# Nixie_Embedded_Controller.net
KiCad netlist of a schematic drawn in Altium Designer
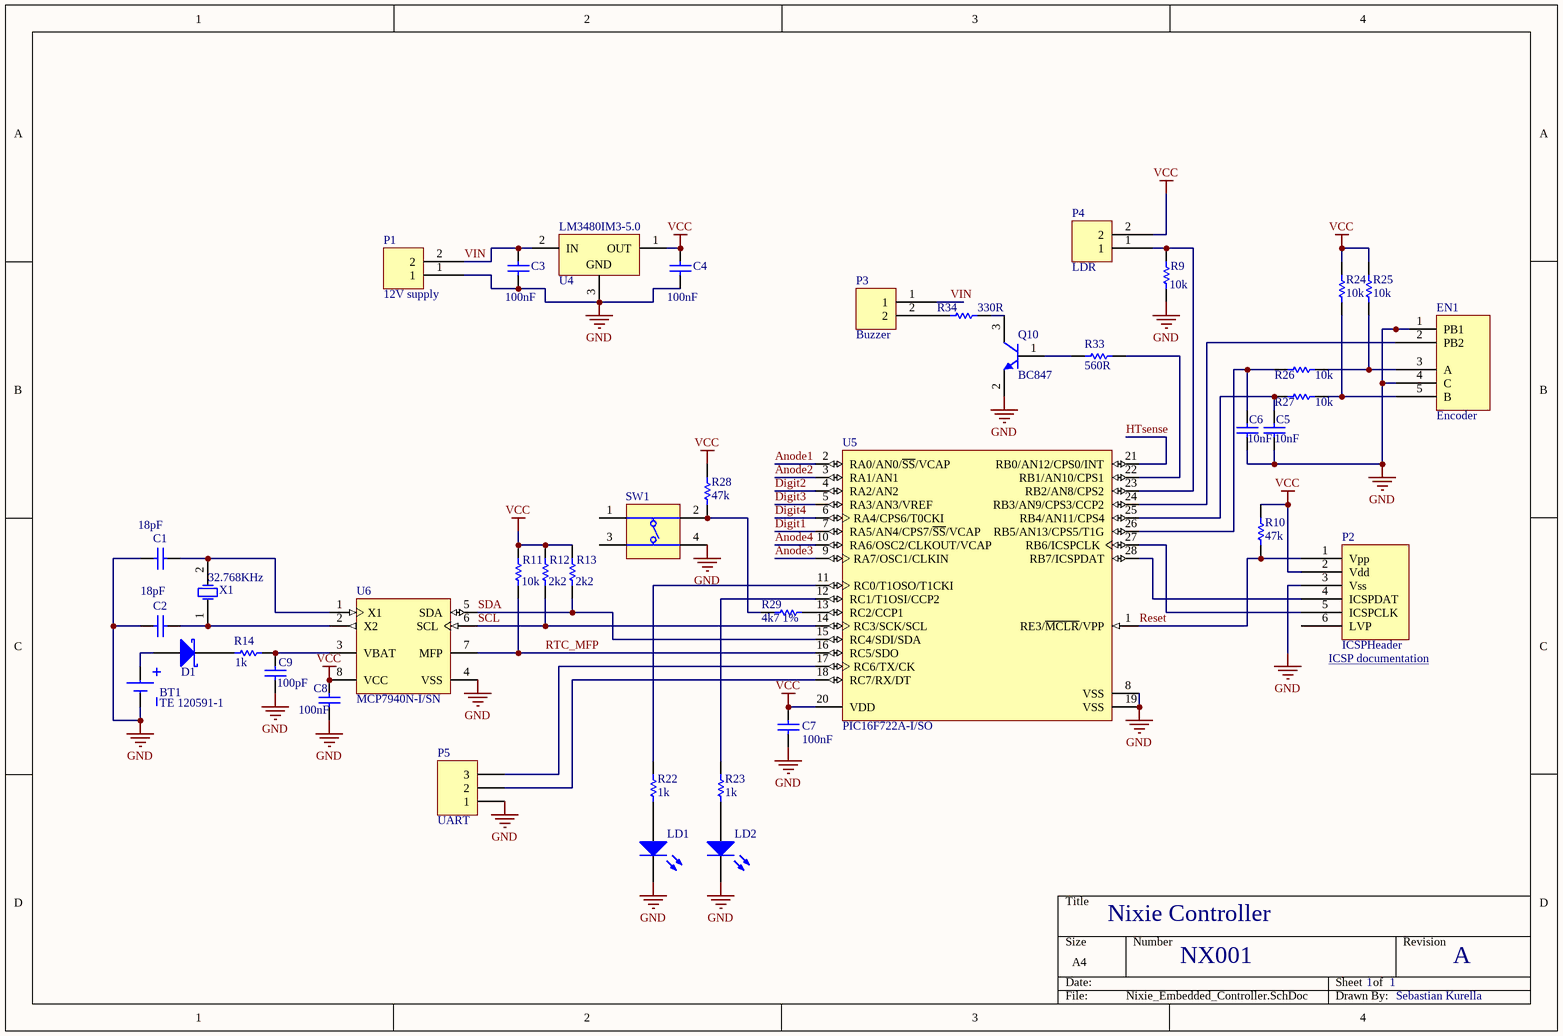
[diagram p0: Nixie_Embedded_Controller.SchDoc]

(export (version "E")
  (design (tool "Eeschema 10.0.6"))
  (components
    (comp (ref "BT1")
      (value "TE 120591-1")
      (footprint "TE-120591-1")
      (libsource (lib "Nixie_Controller") (part "TECO-120591-1-2"))
    )
    (comp (ref "C1")
      (value "18pF")
      (footprint "CAPC0805(2012)100_M")
      (description "CAP 18pF 16V ±5% 0805 (2012 Metric) Thickness 1mm SMD")
      (fields (field (name "TOLERANCE") "±5%") (field (name "Comment") "CAP 18pF 16V 0805(2012)"))
      (libsource (lib "Altium Content Vault") (part "CMP-1036-01121-1"))
    )
    (comp (ref "C2")
      (value "18pF")
      (footprint "CAPC0805(2012)100_M")
      (description "CAP 18pF 16V ±5% 0805 (2012 Metric) Thickness 1mm SMD")
      (fields (field (name "TOLERANCE") "±5%") (field (name "Comment") "CAP 18pF 16V 0805(2012)"))
      (libsource (lib "Altium Content Vault") (part "CMP-1036-01121-1"))
    )
    (comp (ref "C3")
      (value "100nF")
      (footprint "CAPC0805(2012)100_M")
      (description "CAP 100nF 16V ±20% 0805 (2012 Metric) Thickness 1mm SMD")
      (fields (field (name "TOLERANCE") "±20%") (field (name "Comment") "CAP 100nF 16V 0805(2012)"))
      (libsource (lib "Altium Content Vault") (part "CMP-1036-04405-1"))
    )
    (comp (ref "C4")
      (value "100nF")
      (footprint "CAPC0805(2012)100_M")
      (description "CAP 100nF 16V ±20% 0805 (2012 Metric) Thickness 1mm SMD")
      (fields (field (name "TOLERANCE") "±20%") (field (name "Comment") "CAP 100nF 16V 0805(2012)"))
      (libsource (lib "Altium Content Vault") (part "CMP-1036-04405-1"))
    )
    (comp (ref "C5")
      (value "10nF")
      (footprint "CAPC0805(2012)100_M")
      (description "CAP 10nF 16V ±10% 0805 (2012 Metric) Thickness 1mm SMD")
      (fields (field (name "TOLERANCE") "±10%"))
      (libsource (lib "Altium Content Vault") (part "CMP-1036-03820-1"))
    )
    (comp (ref "C6")
      (value "10nF")
      (footprint "CAPC0805(2012)100_M")
      (description "CAP 10nF 16V ±10% 0805 (2012 Metric) Thickness 1mm SMD")
      (fields (field (name "TOLERANCE") "±10%"))
      (libsource (lib "Altium Content Vault") (part "CMP-1036-03820-1"))
    )
    (comp (ref "C7")
      (value "100nF")
      (footprint "CAPC0805(2012)100_M")
      (description "CAP 100nF 10V ±5% 0805 (2012 Metric) Thickness 1mm SMD")
      (fields (field (name "TOLERANCE") "±5%") (field (name "Comment") "CAP 100nF 10V 0805(2012)"))
      (libsource (lib "Altium Content Vault") (part "CAP"))
    )
    (comp (ref "C8")
      (value "100nF")
      (footprint "CAPC0805(2012)100_M")
      (description "CAP 100nF 10V ±5% 0805 (2012 Metric) Thickness 1mm SMD")
      (fields (field (name "TOLERANCE") "±5%") (field (name "Comment") "CAP 100nF 10V 0805(2012)"))
      (libsource (lib "Altium Content Vault") (part "CMP-1036-04393-1"))
    )
    (comp (ref "C9")
      (value "100pF")
      (footprint "CAPC0805(2012)100_M")
      (description "CAP 100pF 10V ±2% 0805 (2012 Metric) Thickness 1mm SMD")
      (fields (field (name "TOLERANCE") "±2%") (field (name "Comment") "CAP 100pF 10V 0805(2012)"))
      (libsource (lib "Altium Content Vault") (part "CMP-1036-01930-1"))
    )
    (comp (ref "D1")
      (value "Schottky")
      (footprint "SOD-123")
      (libsource (lib "Nixie_Controller") (part "Schottky"))
    )
    (comp (ref "EN1")
      (value "Encoder")
      (footprint "BOURNS_PEC12R_ENCODER")
      (libsource (lib "Nixie_Controller") (part "Encoder"))
    )
    (comp (ref "LD1")
      (value "150080GS75000")
      (footprint "0805_A")
      (description "SMD mono-color Chip LED, WL-SMCW, Green")
      (fields (field (name "MANUFACTURER") "Wuerth Elektronik"))
      (libsource (lib "Altium Content Vault") (part "CMP-1426-00007-1"))
    )
    (comp (ref "LD2")
      (value "150080RS75000")
      (footprint "0805_A")
      (description "SMD mono-color Chip LED, WL-SMCW, Red")
      (fields (field (name "MANUFACTURER") "Wuerth Elektronik"))
      (libsource (lib "Altium Content Vault") (part "CMP-1426-00011-1"))
    )
    (comp (ref "P1")
      (value "12V supply")
      (footprint "2pos terminal block 3.5mm")
      (description "TE 1776275-2")
      (libsource (lib "") (part "2pos terminal block 3.5mm_1"))
    )
    (comp (ref "P2")
      (value "ICSPHeader")
      (footprint "ICSPHDR")
      (libsource (lib "Nixie_Controller") (part "ICSPHeader"))
    )
    (comp (ref "P3")
      (value "Buzzer")
      (footprint "2pos terminal block 3.5mm")
      (description "TE 1776275-2")
      (libsource (lib "Nixie_Controller") (part "2pos terminal block 3.5mm"))
    )
    (comp (ref "P4")
      (value "LDR")
      (footprint "Header 1x2")
      (description "TE 640456-2")
      (libsource (lib "Nixie_Controller") (part "Header 1x2"))
    )
    (comp (ref "P5")
      (value "UART")
      (footprint "HDR1X3")
      (description "Header, 3-Pin")
      (fields (field (name "PUBLISHER") "Altium Limited"))
      (libsource (lib "Miscellaneous Connectors") (part "Header 3"))
    )
    (comp (ref "Q10")
      (value "BC847")
      (footprint "ONSC-SOT-23-3-318-08_V")
      (description "General Purpose Transistor, NPN Silicon, 3-Pin SOT-23, Tape and Reel")
      (fields (field (name "MANUFACTURER") "On Semiconductor") (field (name "PARTNUMBER") "BC847ALT1"))
      (libsource (lib "Altium Content Vault") (part "ONSC-NPN-B1E2C3-3"))
    )
    (comp (ref "R9")
      (value "10k")
      (footprint "RESC0805(2012)_M")
      (description "10K 0.125W 5% 0805 (2012 Metric)  SMD")
      (fields (field (name "POWER") "0.125 W") (field (name "TOLERANCE") "5 %"))
      (libsource (lib "Altium Content Vault") (part "CMP-1013-00098-1"))
    )
    (comp (ref "R10")
      (value "47k")
      (footprint "RESC0805(2012)_M")
      (description "47K 0.125W 5% 0805 (2012 Metric)  SMD")
      (fields (field (name "TOLERANCE") "5 %") (field (name "POWER") "0.125 W"))
      (libsource (lib "Altium Content Vault") (part "CMP-1013-00114-1"))
    )
    (comp (ref "R11")
      (value "10k")
      (footprint "RESC0805(2012)_M")
      (description "10K 0.125W 5% 0805 (2012 Metric)  SMD")
      (fields (field (name "POWER") "0.125 W") (field (name "TOLERANCE") "5 %"))
      (libsource (lib "Altium Content Vault") (part "CMP-1013-00098-1"))
    )
    (comp (ref "R12")
      (value "2k2")
      (footprint "RESC0805(2012)_M")
      (description "2K2 0.125W 5% 0805 (2012 Metric)  SMD")
      (fields (field (name "POWER") "0.125 W") (field (name "TOLERANCE") "5 %"))
      (libsource (lib "Altium Content Vault") (part "CMP-1013-00082-1"))
    )
    (comp (ref "R13")
      (value "2k2")
      (footprint "RESC0805(2012)_M")
      (description "2K2 0.125W 5% 0805 (2012 Metric)  SMD")
      (fields (field (name "POWER") "0.125 W") (field (name "TOLERANCE") "5 %"))
      (libsource (lib "Altium Content Vault") (part "CMP-1013-00082-1"))
    )
    (comp (ref "R14")
      (value "1k")
      (footprint "RESC0805(2012)_M")
      (description "1K 0.125W 5% 0805 (2012 Metric)  SMD")
      (fields (field (name "POWER") "0.125 W") (field (name "TOLERANCE") "5 %"))
      (libsource (lib "Altium Content Vault") (part "CMP-1013-00074-1"))
    )
    (comp (ref "R22")
      (value "1k")
      (footprint "RESC0805(2012)_M")
      (description "1K 0.125W 5% 0805 (2012 Metric)  SMD")
      (fields (field (name "POWER") "0.125 W") (field (name "TOLERANCE") "5 %"))
      (libsource (lib "Altium Content Vault") (part "CMP-1013-00074-1"))
    )
    (comp (ref "R23")
      (value "1k")
      (footprint "RESC0805(2012)_M")
      (description "1K 0.125W 5% 0805 (2012 Metric)  SMD")
      (fields (field (name "POWER") "0.125 W") (field (name "TOLERANCE") "5 %"))
      (libsource (lib "Altium Content Vault") (part "CMP-1013-00074-1"))
    )
    (comp (ref "R24")
      (value "10k")
      (footprint "RESC0805(2012)_M")
      (description "10K 0.125W 5% 0805 (2012 Metric)  SMD")
      (fields (field (name "POWER") "0.125 W") (field (name "TOLERANCE") "5 %"))
      (libsource (lib "Altium Content Vault") (part "CMP-1013-00098-1"))
    )
    (comp (ref "R25")
      (value "10k")
      (footprint "RESC0805(2012)_M")
      (description "10K 0.125W 5% 0805 (2012 Metric)  SMD")
      (fields (field (name "POWER") "0.125 W") (field (name "TOLERANCE") "5 %"))
      (libsource (lib "Altium Content Vault") (part "CMP-1013-00098-1"))
    )
    (comp (ref "R26")
      (value "10k")
      (footprint "RESC0805(2012)_M")
      (description "10K 0.125W 5% 0805 (2012 Metric)  SMD")
      (fields (field (name "POWER") "0.125 W") (field (name "TOLERANCE") "5 %"))
      (libsource (lib "Altium Content Vault") (part "CMP-1013-00098-1"))
    )
    (comp (ref "R27")
      (value "10k")
      (footprint "RESC0805(2012)_M")
      (description "10K 0.125W 5% 0805 (2012 Metric)  SMD")
      (fields (field (name "POWER") "0.125 W") (field (name "TOLERANCE") "5 %"))
      (libsource (lib "Altium Content Vault") (part "CMP-1013-00098-1"))
    )
    (comp (ref "R28")
      (value "47k")
      (footprint "RESC0805(2012)_L")
      (description "47K 0.125W 5% 0805 (2012 Metric)  SMD")
      (fields (field (name "TOLERANCE") "5 %") (field (name "POWER") "0.125 W"))
      (libsource (lib "Altium Content Vault") (part "RES"))
    )
    (comp (ref "R29")
      (value "4k7 1%")
      (footprint "RESC0805(2012)_M")
      (description "4K7 0.125W 1% 0805 (2012 Metric)  SMD")
      (fields (field (name "POWER") "0.125 W") (field (name "TOLERANCE") "1 %"))
      (libsource (lib "Altium Content Vault") (part "CMP-1013-00586-1"))
    )
    (comp (ref "R33")
      (value "560R")
      (footprint "RESC0805(2012)_M")
      (description "560R 0.125W 5% 0805 (2012 Metric)  SMD")
      (fields (field (name "POWER") "0.125 W") (field (name "TOLERANCE") "5 %"))
      (libsource (lib "Altium Content Vault") (part "CMP-1013-00068-1"))
    )
    (comp (ref "R34")
      (value "330R")
      (footprint "RESC0805(2012)_M")
      (description "330R 0.125W 5% 0805 (2012 Metric)  SMD")
      (fields (field (name "TOLERANCE") "5 %") (field (name "POWER") "0.125 W"))
      (libsource (lib "Altium Content Vault") (part "CMP-1013-00062-1"))
    )
    (comp (ref "SW1")
      (value "DTSM-61NT/R")
      (footprint "DIPT-DTSM-6_V")
      (description "Switch, SPNO Push Button SMD")
      (fields (field (name "MANUFACTURER") "Diptronics"))
      (libsource (lib "Altium Content Vault") (part "CMP-0306-00001-1"))
    )
    (comp (ref "U4")
      (value "LM3480IM3-5.0")
      (footprint "MF03A_N")
      (description "100 mA, Quasi Low-Dropout Linear Voltage Regulator, 3-pin SOT-23, Pb-Free")
      (fields (field (name "MANUFACTURER") "National Semiconductor"))
      (libsource (lib "Altium Content Vault") (part "PM-REG-LM3480-SOT3"))
    )
    (comp (ref "U5")
      (value "PIC16F722A-I/SO")
      (footprint "MCHP-SOIC-SO28_M")
      (fields (field (name "MANUFACTURER") "Microchip"))
      (libsource (lib "Altium Content Vault") (part "CMP-0115-02602-1"))
    )
    (comp (ref "U6")
      (value "MCP7940N-I/SN")
      (footprint "SOIC-SN8_M")
      (libsource (lib "Altium Content Vault") (part "PR-RTC-MCP7940N-8"))
    )
    (comp (ref "X1")
      (value "32.768KHz")
      (footprint "ABRA-ABS07-2_V")
      (description "Crystal, 32.768 kHz, 12.5 pF, -40 to 85 degC, SMD Low Profile 3.2 x 1.5 x 0.9 mm, Tape and Reel")
      (fields (field (name "PARTNUMBER") "ABS07-32.768KHz-T") (field (name "MANUFACTURER") "Abracon"))
      (libsource (lib "Altium Content Vault") (part "CMP-0447-00001-1"))
    )
  )
  (nets
    (net (code "1") (name "/Anode1") (class "Default")
      (node (ref "U5") (pin "2") (pinfunction "RA0/AN0/~{SS}/VCAP_2") (pintype "bidirectional"))
    )
    (net (code "2") (name "/Anode2") (class "Default")
      (node (ref "U5") (pin "3") (pinfunction "RA1/AN1_3") (pintype "bidirectional"))
    )
    (net (code "3") (name "/Anode3") (class "Default")
      (node (ref "U5") (pin "9") (pinfunction "RA7/OSC1/CLKIN_9") (pintype "bidirectional"))
    )
    (net (code "4") (name "/Anode4") (class "Default")
      (node (ref "U5") (pin "10") (pinfunction "RA6/OSC2/CLKOUT/VCAP_10") (pintype "bidirectional"))
    )
    (net (code "5") (name "/Digit1") (class "Default")
      (node (ref "U5") (pin "7") (pinfunction "RA5/AN4/CPS7/~{SS}/VCAP_7") (pintype "bidirectional"))
    )
    (net (code "6") (name "/Digit2") (class "Default")
      (node (ref "U5") (pin "4") (pinfunction "RA2/AN2_4") (pintype "bidirectional"))
    )
    (net (code "7") (name "/Digit3") (class "Default")
      (node (ref "U5") (pin "5") (pinfunction "RA3/AN3/VREF_5") (pintype "bidirectional"))
    )
    (net (code "8") (name "/Digit4") (class "Default")
      (node (ref "U5") (pin "6") (pinfunction "RA4/CPS6/T0CKI_6") (pintype "bidirectional"))
    )
    (net (code "9") (name "/HTsense") (class "Default")
      (node (ref "U5") (pin "21") (pinfunction "RB0/AN12/CPS0/INT_21") (pintype "bidirectional"))
    )
    (net (code "10") (name "/RTC_MFP") (class "Default")
      (node (ref "R11") (pin "1") (pinfunction "1_1") (pintype "passive"))
      (node (ref "U5") (pin "16") (pinfunction "RC5/SDO_16") (pintype "bidirectional"))
      (node (ref "U6") (pin "7") (pinfunction "MFP_7") (pintype "open_collector"))
    )
    (net (code "11") (name "/Reset") (class "Default")
      (node (ref "P2") (pin "1") (pinfunction "Vpp_1") (pintype "passive"))
      (node (ref "R10") (pin "1") (pinfunction "1_1") (pintype "passive"))
      (node (ref "U5") (pin "1") (pinfunction "RE3/~{MCLR}/VPP_1") (pintype "input"))
    )
    (net (code "12") (name "/SCL") (class "Default")
      (node (ref "R12") (pin "1") (pinfunction "1_1") (pintype "passive"))
      (node (ref "U5") (pin "14") (pinfunction "RC3/SCK/SCL_14") (pintype "bidirectional"))
      (node (ref "U6") (pin "6") (pinfunction "SCL_6") (pintype "input"))
    )
    (net (code "13") (name "/SDA") (class "Default")
      (node (ref "R13") (pin "1") (pinfunction "1_1") (pintype "passive"))
      (node (ref "U5") (pin "15") (pinfunction "RC4/SDI/SDA_15") (pintype "bidirectional"))
      (node (ref "U6") (pin "5") (pinfunction "SDA_5") (pintype "bidirectional"))
    )
    (net (code "14") (name "/VIN") (class "Default")
      (node (ref "C3") (pin "2") (pinfunction "2_2") (pintype "passive"))
      (node (ref "P1") (pin "2") (pinfunction "2_2") (pintype "passive"))
      (node (ref "P3") (pin "1") (pinfunction "1_1") (pintype "passive"))
      (node (ref "U4") (pin "2") (pinfunction "IN_2") (pintype "power_in"))
    )
    (net (code "15") (name "GND") (class "Default")
      (node (ref "BT1") (pin "2") (pinfunction "-_2") (pintype "passive"))
      (node (ref "C1") (pin "1") (pinfunction "1_1") (pintype "passive"))
      (node (ref "C2") (pin "1") (pinfunction "1_1") (pintype "passive"))
      (node (ref "C3") (pin "1") (pinfunction "1_1") (pintype "passive"))
      (node (ref "C4") (pin "1") (pinfunction "1_1") (pintype "passive"))
      (node (ref "C5") (pin "1") (pinfunction "1_1") (pintype "passive"))
      (node (ref "C6") (pin "1") (pinfunction "1_1") (pintype "passive"))
      (node (ref "C7") (pin "1") (pinfunction "1_1") (pintype "passive"))
      (node (ref "C8") (pin "1") (pinfunction "1_1") (pintype "passive"))
      (node (ref "C9") (pin "1") (pinfunction "1_1") (pintype "passive"))
      (node (ref "EN1") (pin "1") (pinfunction "PB1_1") (pintype "passive"))
      (node (ref "EN1") (pin "4") (pinfunction "C_4") (pintype "passive"))
      (node (ref "LD1") (pin "1") (pinfunction "K_1") (pintype "passive"))
      (node (ref "LD2") (pin "1") (pinfunction "K_1") (pintype "passive"))
      (node (ref "P1") (pin "1") (pinfunction "1_1") (pintype "passive"))
      (node (ref "P2") (pin "3") (pinfunction "Vss_3") (pintype "passive"))
      (node (ref "P5") (pin "1") (pinfunction "1_1") (pintype "passive"))
      (node (ref "Q10") (pin "2") (pinfunction "E_2") (pintype "passive"))
      (node (ref "R9") (pin "1") (pinfunction "1_1") (pintype "passive"))
      (node (ref "SW1") (pin "4") (pinfunction "T3_4") (pintype "passive"))
      (node (ref "U4") (pin "3") (pinfunction "GND_3") (pintype "power_in"))
      (node (ref "U5") (pin "19") (pinfunction "VSS_19") (pintype "power_in"))
      (node (ref "U5") (pin "8") (pinfunction "VSS_8") (pintype "power_in"))
      (node (ref "U6") (pin "4") (pinfunction "VSS_4") (pintype "power_in"))
    )
    (net (code "16") (name "Net-(BT1-+)") (class "Default")
      (node (ref "BT1") (pin "1") (pinfunction "+_1") (pintype "passive"))
      (node (ref "D1") (pin "1") (pinfunction "A_1") (pintype "passive"))
    )
    (net (code "17") (name "Net-(D1-K)") (class "Default")
      (node (ref "D1") (pin "2") (pinfunction "K_2") (pintype "passive"))
      (node (ref "R14") (pin "1") (pinfunction "1_1") (pintype "passive"))
    )
    (net (code "18") (name "Net-(EN1-A)") (class "Default")
      (node (ref "EN1") (pin "3") (pinfunction "A_3") (pintype "passive"))
      (node (ref "R25") (pin "1") (pinfunction "1_1") (pintype "passive"))
      (node (ref "R26") (pin "1") (pinfunction "1_1") (pintype "passive"))
    )
    (net (code "19") (name "Net-(EN1-B)") (class "Default")
      (node (ref "EN1") (pin "5") (pinfunction "B_5") (pintype "passive"))
      (node (ref "R24") (pin "1") (pinfunction "1_1") (pintype "passive"))
      (node (ref "R27") (pin "1") (pinfunction "1_1") (pintype "passive"))
    )
    (net (code "20") (name "Net-(EN1-PB2)") (class "Default")
      (node (ref "EN1") (pin "2") (pinfunction "PB2_2") (pintype "passive"))
      (node (ref "U5") (pin "24") (pinfunction "RB3/AN9/CPS3/CCP2_24") (pintype "bidirectional"))
    )
    (net (code "21") (name "Net-(LD1-A)") (class "Default")
      (node (ref "LD1") (pin "2") (pinfunction "A_2") (pintype "passive"))
      (node (ref "R22") (pin "1") (pinfunction "1_1") (pintype "passive"))
    )
    (net (code "22") (name "Net-(LD2-A)") (class "Default")
      (node (ref "LD2") (pin "2") (pinfunction "A_2") (pintype "passive"))
      (node (ref "R23") (pin "1") (pinfunction "1_1") (pintype "passive"))
    )
    (net (code "23") (name "Net-(P2-ICSPCLK)") (class "Default")
      (node (ref "P2") (pin "5") (pinfunction "ICSPCLK_5") (pintype "passive"))
      (node (ref "U5") (pin "27") (pinfunction "RB6/ICSPCLK_27") (pintype "bidirectional"))
    )
    (net (code "24") (name "Net-(P2-ICSPDAT)") (class "Default")
      (node (ref "P2") (pin "4") (pinfunction "ICSPDAT_4") (pintype "passive"))
      (node (ref "U5") (pin "28") (pinfunction "RB7/ICSPDAT_28") (pintype "bidirectional"))
    )
    (net (code "25") (name "Net-(P3-Pad2)") (class "Default")
      (node (ref "P3") (pin "2") (pinfunction "2_2") (pintype "passive"))
      (node (ref "R34") (pin "1") (pinfunction "1_1") (pintype "passive"))
    )
    (net (code "26") (name "Net-(Q10-B)") (class "Default")
      (node (ref "Q10") (pin "1") (pinfunction "B_1") (pintype "passive"))
      (node (ref "R33") (pin "1") (pinfunction "1_1") (pintype "passive"))
    )
    (net (code "27") (name "Net-(Q10-C)") (class "Default")
      (node (ref "Q10") (pin "3") (pinfunction "C_3") (pintype "passive"))
      (node (ref "R34") (pin "2") (pinfunction "2_2") (pintype "passive"))
    )
    (net (code "28") (name "Net-(SW1-T2)") (class "Default")
      (node (ref "R28") (pin "1") (pinfunction "1_1") (pintype "passive"))
      (node (ref "R29") (pin "2") (pinfunction "2_2") (pintype "passive"))
      (node (ref "SW1") (pin "2") (pinfunction "T2_2") (pintype "passive"))
    )
    (net (code "29") (name "Net-(U5-RB1{slash}AN10{slash}CPS1)") (class "Default")
      (node (ref "R33") (pin "2") (pinfunction "2_2") (pintype "passive"))
      (node (ref "U5") (pin "22") (pinfunction "RB1/AN10/CPS1_22") (pintype "bidirectional"))
    )
    (net (code "30") (name "Net-(U5-RB2{slash}AN8{slash}CPS2)") (class "Default")
      (node (ref "P4") (pin "1") (pinfunction "1_1") (pintype "passive"))
      (node (ref "R9") (pin "2") (pinfunction "2_2") (pintype "passive"))
      (node (ref "U5") (pin "23") (pinfunction "RB2/AN8/CPS2_23") (pintype "bidirectional"))
    )
    (net (code "31") (name "Net-(U5-RB4{slash}AN11{slash}CPS4)") (class "Default")
      (node (ref "C5") (pin "2") (pinfunction "2_2") (pintype "passive"))
      (node (ref "R27") (pin "2") (pinfunction "2_2") (pintype "passive"))
      (node (ref "U5") (pin "25") (pinfunction "RB4/AN11/CPS4_25") (pintype "bidirectional"))
    )
    (net (code "32") (name "Net-(U5-RB5{slash}AN13{slash}CPS5{slash}T1G)") (class "Default")
      (node (ref "C6") (pin "2") (pinfunction "2_2") (pintype "passive"))
      (node (ref "R26") (pin "2") (pinfunction "2_2") (pintype "passive"))
      (node (ref "U5") (pin "26") (pinfunction "RB5/AN13/CPS5/T1G_26") (pintype "bidirectional"))
    )
    (net (code "33") (name "Net-(U5-RC0{slash}T1OSO{slash}T1CKI)") (class "Default")
      (node (ref "R22") (pin "2") (pinfunction "2_2") (pintype "passive"))
      (node (ref "U5") (pin "11") (pinfunction "RC0/T1OSO/T1CKI_11") (pintype "bidirectional"))
    )
    (net (code "34") (name "Net-(U5-RC1{slash}T1OSI{slash}CCP2)") (class "Default")
      (node (ref "R23") (pin "2") (pinfunction "2_2") (pintype "passive"))
      (node (ref "U5") (pin "12") (pinfunction "RC1/T1OSI/CCP2_12") (pintype "bidirectional"))
    )
    (net (code "35") (name "Net-(U5-RC2{slash}CCP1)") (class "Default")
      (node (ref "R29") (pin "1") (pinfunction "1_1") (pintype "passive"))
      (node (ref "U5") (pin "13") (pinfunction "RC2/CCP1_13") (pintype "bidirectional"))
    )
    (net (code "36") (name "Net-(U5-RC6{slash}TX{slash}CK)") (class "Default")
      (node (ref "P5") (pin "3") (pinfunction "3_3") (pintype "passive"))
      (node (ref "U5") (pin "17") (pinfunction "RC6/TX/CK_17") (pintype "bidirectional"))
    )
    (net (code "37") (name "Net-(U5-RC7{slash}RX{slash}DT)") (class "Default")
      (node (ref "P5") (pin "2") (pinfunction "2_2") (pintype "passive"))
      (node (ref "U5") (pin "18") (pinfunction "RC7/RX/DT_18") (pintype "bidirectional"))
    )
    (net (code "38") (name "Net-(U6-VBAT)") (class "Default")
      (node (ref "C9") (pin "2") (pinfunction "2_2") (pintype "passive"))
      (node (ref "R14") (pin "2") (pinfunction "2_2") (pintype "passive"))
      (node (ref "U6") (pin "3") (pinfunction "VBAT_3") (pintype "power_in"))
    )
    (net (code "39") (name "Net-(U6-X1)") (class "Default")
      (node (ref "C1") (pin "2") (pinfunction "2_2") (pintype "passive"))
      (node (ref "U6") (pin "1") (pinfunction "X1_1") (pintype "input"))
      (node (ref "X1") (pin "2") (pinfunction "X2_2") (pintype "passive"))
    )
    (net (code "40") (name "Net-(U6-X2)") (class "Default")
      (node (ref "C2") (pin "2") (pinfunction "2_2") (pintype "passive"))
      (node (ref "U6") (pin "2") (pinfunction "X2_2") (pintype "output"))
      (node (ref "X1") (pin "1") (pinfunction "X1_1") (pintype "passive"))
    )
    (net (code "41") (name "VCC") (class "Default")
      (node (ref "C4") (pin "2") (pinfunction "2_2") (pintype "passive"))
      (node (ref "C7") (pin "2") (pinfunction "2_2") (pintype "passive"))
      (node (ref "C8") (pin "2") (pinfunction "2_2") (pintype "passive"))
      (node (ref "P2") (pin "2") (pinfunction "Vdd_2") (pintype "passive"))
      (node (ref "P4") (pin "2") (pinfunction "2_2") (pintype "passive"))
      (node (ref "R10") (pin "2") (pinfunction "2_2") (pintype "passive"))
      (node (ref "R11") (pin "2") (pinfunction "2_2") (pintype "passive"))
      (node (ref "R12") (pin "2") (pinfunction "2_2") (pintype "passive"))
      (node (ref "R13") (pin "2") (pinfunction "2_2") (pintype "passive"))
      (node (ref "R24") (pin "2") (pinfunction "2_2") (pintype "passive"))
      (node (ref "R25") (pin "2") (pinfunction "2_2") (pintype "passive"))
      (node (ref "R28") (pin "2") (pinfunction "2_2") (pintype "passive"))
      (node (ref "U4") (pin "1") (pinfunction "OUT_1") (pintype "power_in"))
      (node (ref "U5") (pin "20") (pinfunction "VDD_20") (pintype "power_in"))
      (node (ref "U6") (pin "8") (pinfunction "VCC_8") (pintype "power_in"))
    )
    (net (code "42") (name "unconnected-(P2-LVP-Pad6)") (class "Default")
      (node (ref "P2") (pin "6") (pinfunction "LVP_6") (pintype "passive"))
    )
    (net (code "43") (name "unconnected-(SW1-T1-Pad1)") (class "Default")
      (node (ref "SW1") (pin "1") (pinfunction "T1_1") (pintype "passive"))
    )
    (net (code "44") (name "unconnected-(SW1-T3-Pad3)") (class "Default")
      (node (ref "SW1") (pin "3") (pinfunction "T3_3") (pintype "passive"))
    )
  )
)
